# Digital_Port_F_State_LED_Inducator.net
KiCad netlist of a schematic drawn in Altium Designer
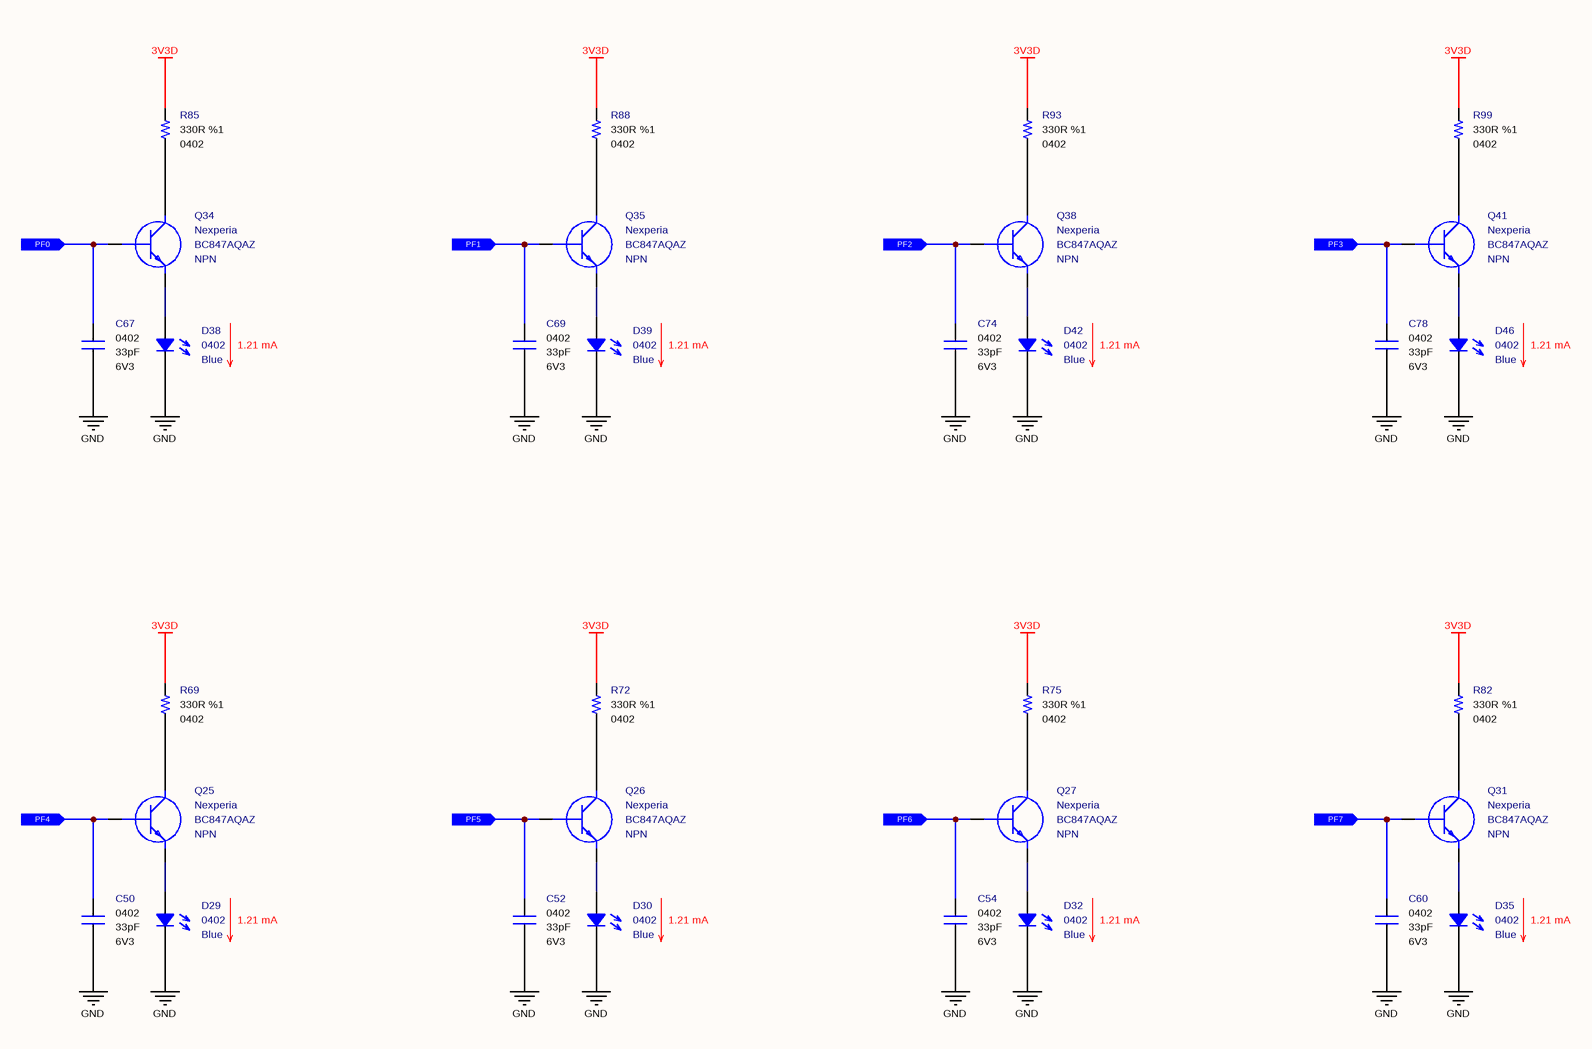
[diagram p0: Digital Port F State LED Inducator.SchDoc]

(export (version "E")
  (design (tool "Eeschema 10.0.6"))
  (components
    (comp (ref "C50")
      (value "33pF")
      (footprint "CAPACITOR_0402")
      (description "Capacitor - 33pF [0402] (Ceramic)")
      (fields
        (field (name "CASE") "0402")
        (field (name "TOLERANCE") "10%")
        (field (name "VOLTAGE") "6V3")
        (field (name "MANUFACTURER PART NUMBER") "C0402C330J9RACAUTO")
      )
      (libsource (lib "Ovoo_Library") (part "Capacitor - 33pF [0402-6V3]"))
    )
    (comp (ref "C52")
      (value "33pF")
      (footprint "CAPACITOR_0402")
      (description "Capacitor - 33pF [0402] (Ceramic)")
      (fields
        (field (name "CASE") "0402")
        (field (name "TOLERANCE") "10%")
        (field (name "VOLTAGE") "6V3")
        (field (name "MANUFACTURER PART NUMBER") "C0402C330J9RACAUTO")
      )
      (libsource (lib "Ovoo_Library") (part "Capacitor - 33pF [0402-6V3]"))
    )
    (comp (ref "C54")
      (value "33pF")
      (footprint "CAPACITOR_0402")
      (description "Capacitor - 33pF [0402] (Ceramic)")
      (fields
        (field (name "CASE") "0402")
        (field (name "TOLERANCE") "10%")
        (field (name "VOLTAGE") "6V3")
        (field (name "MANUFACTURER PART NUMBER") "C0402C330J9RACAUTO")
      )
      (libsource (lib "Ovoo_Library") (part "Capacitor - 33pF [0402-6V3]"))
    )
    (comp (ref "C60")
      (value "33pF")
      (footprint "CAPACITOR_0402")
      (description "Capacitor - 33pF [0402] (Ceramic)")
      (fields
        (field (name "CASE") "0402")
        (field (name "TOLERANCE") "10%")
        (field (name "VOLTAGE") "6V3")
        (field (name "MANUFACTURER PART NUMBER") "C0402C330J9RACAUTO")
      )
      (libsource (lib "Ovoo_Library") (part "Capacitor - 33pF [0402-6V3]"))
    )
    (comp (ref "C67")
      (value "33pF")
      (footprint "CAPACITOR_0402")
      (description "Capacitor - 33pF [0402] (Ceramic)")
      (fields
        (field (name "CASE") "0402")
        (field (name "TOLERANCE") "10%")
        (field (name "VOLTAGE") "6V3")
        (field (name "MANUFACTURER PART NUMBER") "C0402C330J9RACAUTO")
      )
      (libsource (lib "Ovoo_Library") (part "Capacitor - 33pF [0402-6V3]"))
    )
    (comp (ref "C69")
      (value "33pF")
      (footprint "CAPACITOR_0402")
      (description "Capacitor - 33pF [0402] (Ceramic)")
      (fields
        (field (name "CASE") "0402")
        (field (name "TOLERANCE") "10%")
        (field (name "VOLTAGE") "6V3")
        (field (name "MANUFACTURER PART NUMBER") "C0402C330J9RACAUTO")
      )
      (libsource (lib "Ovoo_Library") (part "Capacitor - 33pF [0402-6V3]"))
    )
    (comp (ref "C74")
      (value "33pF")
      (footprint "CAPACITOR_0402")
      (description "Capacitor - 33pF [0402] (Ceramic)")
      (fields
        (field (name "CASE") "0402")
        (field (name "TOLERANCE") "10%")
        (field (name "VOLTAGE") "6V3")
        (field (name "MANUFACTURER PART NUMBER") "C0402C330J9RACAUTO")
      )
      (libsource (lib "Ovoo_Library") (part "Capacitor - 33pF [0402-6V3]"))
    )
    (comp (ref "C78")
      (value "33pF")
      (footprint "CAPACITOR_0402")
      (description "Capacitor - 33pF [0402] (Ceramic)")
      (fields
        (field (name "CASE") "0402")
        (field (name "TOLERANCE") "10%")
        (field (name "VOLTAGE") "6V3")
        (field (name "MANUFACTURER PART NUMBER") "C0402C330J9RACAUTO")
      )
      (libsource (lib "Ovoo_Library") (part "Capacitor - 33pF [0402-6V3]"))
    )
    (comp (ref "D29")
      (value "SMD LED (Blue)")
      (footprint "LED_0402")
      (description "Standard LEDs - SMD PICOLEDTM;BLUE LED; 25M @ 5MA")
      (fields
        (field (name "MANUFACTURER_PART_NUMBER") "SMLP13BC8TT86")
        (field (name "MOUSER_PART_NUMBER") "755-SMLP13BC8TT86")
        (field (name "CASE") "0402")
        (field (name "COLOR") "Blue")
      )
      (libsource (lib "Ovoo_Library") (part "Diode - LED (0402-Blue)"))
    )
    (comp (ref "D30")
      (value "SMD LED (Blue)")
      (footprint "LED_0402")
      (description "Standard LEDs - SMD PICOLEDTM;BLUE LED; 25M @ 5MA")
      (fields
        (field (name "MANUFACTURER_PART_NUMBER") "SMLP13BC8TT86")
        (field (name "MOUSER_PART_NUMBER") "755-SMLP13BC8TT86")
        (field (name "CASE") "0402")
        (field (name "COLOR") "Blue")
      )
      (libsource (lib "Ovoo_Library") (part "Diode - LED (0402-Blue)"))
    )
    (comp (ref "D32")
      (value "SMD LED (Blue)")
      (footprint "LED_0402")
      (description "Standard LEDs - SMD PICOLEDTM;BLUE LED; 25M @ 5MA")
      (fields
        (field (name "MANUFACTURER_PART_NUMBER") "SMLP13BC8TT86")
        (field (name "MOUSER_PART_NUMBER") "755-SMLP13BC8TT86")
        (field (name "CASE") "0402")
        (field (name "COLOR") "Blue")
      )
      (libsource (lib "Ovoo_Library") (part "Diode - LED (0402-Blue)"))
    )
    (comp (ref "D35")
      (value "SMD LED (Blue)")
      (footprint "LED_0402")
      (description "Standard LEDs - SMD PICOLEDTM;BLUE LED; 25M @ 5MA")
      (fields
        (field (name "MANUFACTURER_PART_NUMBER") "SMLP13BC8TT86")
        (field (name "MOUSER_PART_NUMBER") "755-SMLP13BC8TT86")
        (field (name "CASE") "0402")
        (field (name "COLOR") "Blue")
      )
      (libsource (lib "Ovoo_Library") (part "Diode - LED (0402-Blue)"))
    )
    (comp (ref "D38")
      (value "SMD LED (Blue)")
      (footprint "LED_0402")
      (description "Standard LEDs - SMD PICOLEDTM;BLUE LED; 25M @ 5MA")
      (fields
        (field (name "MANUFACTURER_PART_NUMBER") "SMLP13BC8TT86")
        (field (name "MOUSER_PART_NUMBER") "755-SMLP13BC8TT86")
        (field (name "CASE") "0402")
        (field (name "COLOR") "Blue")
      )
      (libsource (lib "Ovoo_Library") (part "Diode - LED (0402-Blue)"))
    )
    (comp (ref "D39")
      (value "SMD LED (Blue)")
      (footprint "LED_0402")
      (description "Standard LEDs - SMD PICOLEDTM;BLUE LED; 25M @ 5MA")
      (fields
        (field (name "MANUFACTURER_PART_NUMBER") "SMLP13BC8TT86")
        (field (name "MOUSER_PART_NUMBER") "755-SMLP13BC8TT86")
        (field (name "CASE") "0402")
        (field (name "COLOR") "Blue")
      )
      (libsource (lib "Ovoo_Library") (part "Diode - LED (0402-Blue)"))
    )
    (comp (ref "D42")
      (value "SMD LED (Blue)")
      (footprint "LED_0402")
      (description "Standard LEDs - SMD PICOLEDTM;BLUE LED; 25M @ 5MA")
      (fields
        (field (name "MANUFACTURER_PART_NUMBER") "SMLP13BC8TT86")
        (field (name "MOUSER_PART_NUMBER") "755-SMLP13BC8TT86")
        (field (name "CASE") "0402")
        (field (name "COLOR") "Blue")
      )
      (libsource (lib "Ovoo_Library") (part "Diode - LED (0402-Blue)"))
    )
    (comp (ref "D46")
      (value "SMD LED (Blue)")
      (footprint "LED_0402")
      (description "Standard LEDs - SMD PICOLEDTM;BLUE LED; 25M @ 5MA")
      (fields
        (field (name "MANUFACTURER_PART_NUMBER") "SMLP13BC8TT86")
        (field (name "MOUSER_PART_NUMBER") "755-SMLP13BC8TT86")
        (field (name "CASE") "0402")
        (field (name "COLOR") "Blue")
      )
      (libsource (lib "Ovoo_Library") (part "Diode - LED (0402-Blue)"))
    )
    (comp (ref "Q25")
      (value "Bipolar NPN Transistors")
      (footprint "SOT1215")
      (description "Bipolar Transistors - BJT BC847AQA/DFN1010D-3/REEL 7\" Q2")
      (fields
        (field (name "MOUSER_PART_NUMBER") "771-BC847AQAZ")
        (field (name "MANUFACTURER_NAME") "Nexperia")
        (field (name "MANUFACTURER_PART_NUMBER") "BC847AQAZ")
        (field (name "POLARITY") "NPN")
      )
      (libsource (lib "Ovoo_Library") (part "Transistor - BC847"))
    )
    (comp (ref "Q26")
      (value "Bipolar NPN Transistors")
      (footprint "SOT1215")
      (description "Bipolar Transistors - BJT BC847AQA/DFN1010D-3/REEL 7\" Q2")
      (fields
        (field (name "MOUSER_PART_NUMBER") "771-BC847AQAZ")
        (field (name "MANUFACTURER_NAME") "Nexperia")
        (field (name "MANUFACTURER_PART_NUMBER") "BC847AQAZ")
        (field (name "POLARITY") "NPN")
      )
      (libsource (lib "Ovoo_Library") (part "Transistor - BC847"))
    )
    (comp (ref "Q27")
      (value "Bipolar NPN Transistors")
      (footprint "SOT1215")
      (description "Bipolar Transistors - BJT BC847AQA/DFN1010D-3/REEL 7\" Q2")
      (fields
        (field (name "MOUSER_PART_NUMBER") "771-BC847AQAZ")
        (field (name "MANUFACTURER_NAME") "Nexperia")
        (field (name "MANUFACTURER_PART_NUMBER") "BC847AQAZ")
        (field (name "POLARITY") "NPN")
      )
      (libsource (lib "Ovoo_Library") (part "Transistor - BC847"))
    )
    (comp (ref "Q31")
      (value "Bipolar NPN Transistors")
      (footprint "SOT1215")
      (description "Bipolar Transistors - BJT BC847AQA/DFN1010D-3/REEL 7\" Q2")
      (fields
        (field (name "MOUSER_PART_NUMBER") "771-BC847AQAZ")
        (field (name "MANUFACTURER_NAME") "Nexperia")
        (field (name "MANUFACTURER_PART_NUMBER") "BC847AQAZ")
        (field (name "POLARITY") "NPN")
      )
      (libsource (lib "Ovoo_Library") (part "Transistor - BC847"))
    )
    (comp (ref "Q34")
      (value "Bipolar NPN Transistors")
      (footprint "SOT1215")
      (description "Bipolar Transistors - BJT BC847AQA/DFN1010D-3/REEL 7\" Q2")
      (fields
        (field (name "MOUSER_PART_NUMBER") "771-BC847AQAZ")
        (field (name "MANUFACTURER_NAME") "Nexperia")
        (field (name "MANUFACTURER_PART_NUMBER") "BC847AQAZ")
        (field (name "POLARITY") "NPN")
      )
      (libsource (lib "Ovoo_Library") (part "Transistor - BC847"))
    )
    (comp (ref "Q35")
      (value "Bipolar NPN Transistors")
      (footprint "SOT1215")
      (description "Bipolar Transistors - BJT BC847AQA/DFN1010D-3/REEL 7\" Q2")
      (fields
        (field (name "MOUSER_PART_NUMBER") "771-BC847AQAZ")
        (field (name "MANUFACTURER_NAME") "Nexperia")
        (field (name "MANUFACTURER_PART_NUMBER") "BC847AQAZ")
        (field (name "POLARITY") "NPN")
      )
      (libsource (lib "Ovoo_Library") (part "Transistor - BC847"))
    )
    (comp (ref "Q38")
      (value "Bipolar NPN Transistors")
      (footprint "SOT1215")
      (description "Bipolar Transistors - BJT BC847AQA/DFN1010D-3/REEL 7\" Q2")
      (fields
        (field (name "MOUSER_PART_NUMBER") "771-BC847AQAZ")
        (field (name "MANUFACTURER_NAME") "Nexperia")
        (field (name "MANUFACTURER_PART_NUMBER") "BC847AQAZ")
        (field (name "POLARITY") "NPN")
      )
      (libsource (lib "Ovoo_Library") (part "Transistor - BC847"))
    )
    (comp (ref "Q41")
      (value "Bipolar NPN Transistors")
      (footprint "SOT1215")
      (description "Bipolar Transistors - BJT BC847AQA/DFN1010D-3/REEL 7\" Q2")
      (fields
        (field (name "MOUSER_PART_NUMBER") "771-BC847AQAZ")
        (field (name "MANUFACTURER_NAME") "Nexperia")
        (field (name "MANUFACTURER_PART_NUMBER") "BC847AQAZ")
        (field (name "POLARITY") "NPN")
      )
      (libsource (lib "Ovoo_Library") (part "Transistor - BC847"))
    )
    (comp (ref "R69")
      (value "330R")
      (footprint "RESISTOR_0402")
      (description "Thick Film Resistors - SMD 1/16 W 330 Ohm 1%")
      (fields
        (field (name "TOLERANCE") "%1")
        (field (name "CASE") "0402")
        (field (name "MANUFACTURER PART NUMBER") "CRCW0402330RFKED")
        (field (name "MOUSER PART NUMBER") "71-CRCW0402-330-E3")
      )
      (libsource (lib "Ovoo_Library") (part "Resistor - 330R"))
    )
    (comp (ref "R72")
      (value "330R")
      (footprint "RESISTOR_0402")
      (description "Thick Film Resistors - SMD 1/16 W 330 Ohm 1%")
      (fields
        (field (name "TOLERANCE") "%1")
        (field (name "CASE") "0402")
        (field (name "MANUFACTURER PART NUMBER") "CRCW0402330RFKED")
        (field (name "MOUSER PART NUMBER") "71-CRCW0402-330-E3")
      )
      (libsource (lib "Ovoo_Library") (part "Resistor - 330R"))
    )
    (comp (ref "R75")
      (value "330R")
      (footprint "RESISTOR_0402")
      (description "Thick Film Resistors - SMD 1/16 W 330 Ohm 1%")
      (fields
        (field (name "TOLERANCE") "%1")
        (field (name "CASE") "0402")
        (field (name "MANUFACTURER PART NUMBER") "CRCW0402330RFKED")
        (field (name "MOUSER PART NUMBER") "71-CRCW0402-330-E3")
      )
      (libsource (lib "Ovoo_Library") (part "Resistor - 330R"))
    )
    (comp (ref "R82")
      (value "330R")
      (footprint "RESISTOR_0402")
      (description "Thick Film Resistors - SMD 1/16 W 330 Ohm 1%")
      (fields
        (field (name "TOLERANCE") "%1")
        (field (name "CASE") "0402")
        (field (name "MANUFACTURER PART NUMBER") "CRCW0402330RFKED")
        (field (name "MOUSER PART NUMBER") "71-CRCW0402-330-E3")
      )
      (libsource (lib "Ovoo_Library") (part "Resistor - 330R"))
    )
    (comp (ref "R85")
      (value "330R")
      (footprint "RESISTOR_0402")
      (description "Thick Film Resistors - SMD 1/16 W 330 Ohm 1%")
      (fields
        (field (name "TOLERANCE") "%1")
        (field (name "CASE") "0402")
        (field (name "MANUFACTURER PART NUMBER") "CRCW0402330RFKED")
        (field (name "MOUSER PART NUMBER") "71-CRCW0402-330-E3")
      )
      (libsource (lib "Ovoo_Library") (part "Resistor - 330R"))
    )
    (comp (ref "R88")
      (value "330R")
      (footprint "RESISTOR_0402")
      (description "Thick Film Resistors - SMD 1/16 W 330 Ohm 1%")
      (fields
        (field (name "TOLERANCE") "%1")
        (field (name "CASE") "0402")
        (field (name "MANUFACTURER PART NUMBER") "CRCW0402330RFKED")
        (field (name "MOUSER PART NUMBER") "71-CRCW0402-330-E3")
      )
      (libsource (lib "Ovoo_Library") (part "Resistor - 330R"))
    )
    (comp (ref "R93")
      (value "330R")
      (footprint "RESISTOR_0402")
      (description "Thick Film Resistors - SMD 1/16 W 330 Ohm 1%")
      (fields
        (field (name "TOLERANCE") "%1")
        (field (name "CASE") "0402")
        (field (name "MANUFACTURER PART NUMBER") "CRCW0402330RFKED")
        (field (name "MOUSER PART NUMBER") "71-CRCW0402-330-E3")
      )
      (libsource (lib "Ovoo_Library") (part "Resistor - 330R"))
    )
    (comp (ref "R99")
      (value "330R")
      (footprint "RESISTOR_0402")
      (description "Thick Film Resistors - SMD 1/16 W 330 Ohm 1%")
      (fields
        (field (name "TOLERANCE") "%1")
        (field (name "CASE") "0402")
        (field (name "MANUFACTURER PART NUMBER") "CRCW0402330RFKED")
        (field (name "MOUSER PART NUMBER") "71-CRCW0402-330-E3")
      )
      (libsource (lib "Ovoo_Library") (part "Resistor - 330R"))
    )
  )
  (nets
    (net (code "1") (name "/PF0") (class "Default")
      (node (ref "C67") (pin "1") (pinfunction "1_1") (pintype "passive"))
      (node (ref "Q34") (pin "1") (pinfunction "B_1") (pintype "passive"))
    )
    (net (code "2") (name "/PF1") (class "Default")
      (node (ref "C69") (pin "1") (pinfunction "1_1") (pintype "passive"))
      (node (ref "Q35") (pin "1") (pinfunction "B_1") (pintype "passive"))
    )
    (net (code "3") (name "/PF2") (class "Default")
      (node (ref "C74") (pin "1") (pinfunction "1_1") (pintype "passive"))
      (node (ref "Q38") (pin "1") (pinfunction "B_1") (pintype "passive"))
    )
    (net (code "4") (name "/PF3") (class "Default")
      (node (ref "C78") (pin "1") (pinfunction "1_1") (pintype "passive"))
      (node (ref "Q41") (pin "1") (pinfunction "B_1") (pintype "passive"))
    )
    (net (code "5") (name "/PF4") (class "Default")
      (node (ref "C50") (pin "1") (pinfunction "1_1") (pintype "passive"))
      (node (ref "Q25") (pin "1") (pinfunction "B_1") (pintype "passive"))
    )
    (net (code "6") (name "/PF5") (class "Default")
      (node (ref "C52") (pin "1") (pinfunction "1_1") (pintype "passive"))
      (node (ref "Q26") (pin "1") (pinfunction "B_1") (pintype "passive"))
    )
    (net (code "7") (name "/PF6") (class "Default")
      (node (ref "C54") (pin "1") (pinfunction "1_1") (pintype "passive"))
      (node (ref "Q27") (pin "1") (pinfunction "B_1") (pintype "passive"))
    )
    (net (code "8") (name "/PF7") (class "Default")
      (node (ref "C60") (pin "1") (pinfunction "1_1") (pintype "passive"))
      (node (ref "Q31") (pin "1") (pinfunction "B_1") (pintype "passive"))
    )
    (net (code "9") (name "3V3D") (class "Default")
      (node (ref "R69") (pin "2") (pinfunction "2_2") (pintype "passive"))
      (node (ref "R72") (pin "2") (pinfunction "2_2") (pintype "passive"))
      (node (ref "R75") (pin "2") (pinfunction "2_2") (pintype "passive"))
      (node (ref "R82") (pin "2") (pinfunction "2_2") (pintype "passive"))
      (node (ref "R85") (pin "2") (pinfunction "2_2") (pintype "passive"))
      (node (ref "R88") (pin "2") (pinfunction "2_2") (pintype "passive"))
      (node (ref "R93") (pin "2") (pinfunction "2_2") (pintype "passive"))
      (node (ref "R99") (pin "2") (pinfunction "2_2") (pintype "passive"))
    )
    (net (code "10") (name "GND") (class "Default")
      (node (ref "C50") (pin "2") (pinfunction "2_2") (pintype "passive"))
      (node (ref "C52") (pin "2") (pinfunction "2_2") (pintype "passive"))
      (node (ref "C54") (pin "2") (pinfunction "2_2") (pintype "passive"))
      (node (ref "C60") (pin "2") (pinfunction "2_2") (pintype "passive"))
      (node (ref "C67") (pin "2") (pinfunction "2_2") (pintype "passive"))
      (node (ref "C69") (pin "2") (pinfunction "2_2") (pintype "passive"))
      (node (ref "C74") (pin "2") (pinfunction "2_2") (pintype "passive"))
      (node (ref "C78") (pin "2") (pinfunction "2_2") (pintype "passive"))
      (node (ref "D29") (pin "1") (pinfunction "1_1") (pintype "passive"))
      (node (ref "D30") (pin "1") (pinfunction "1_1") (pintype "passive"))
      (node (ref "D32") (pin "1") (pinfunction "1_1") (pintype "passive"))
      (node (ref "D35") (pin "1") (pinfunction "1_1") (pintype "passive"))
      (node (ref "D38") (pin "1") (pinfunction "1_1") (pintype "passive"))
      (node (ref "D39") (pin "1") (pinfunction "1_1") (pintype "passive"))
      (node (ref "D42") (pin "1") (pinfunction "1_1") (pintype "passive"))
      (node (ref "D46") (pin "1") (pinfunction "1_1") (pintype "passive"))
    )
    (net (code "11") (name "Net-(Q25-C)") (class "Default")
      (node (ref "Q25") (pin "3") (pinfunction "C_3") (pintype "passive"))
      (node (ref "R69") (pin "1") (pinfunction "1_1") (pintype "passive"))
    )
    (net (code "12") (name "Net-(Q25-E)") (class "Default")
      (node (ref "D29") (pin "2") (pinfunction "2_2") (pintype "passive"))
      (node (ref "Q25") (pin "2") (pinfunction "E_2") (pintype "passive"))
    )
    (net (code "13") (name "Net-(Q26-C)") (class "Default")
      (node (ref "Q26") (pin "3") (pinfunction "C_3") (pintype "passive"))
      (node (ref "R72") (pin "1") (pinfunction "1_1") (pintype "passive"))
    )
    (net (code "14") (name "Net-(Q26-E)") (class "Default")
      (node (ref "D30") (pin "2") (pinfunction "2_2") (pintype "passive"))
      (node (ref "Q26") (pin "2") (pinfunction "E_2") (pintype "passive"))
    )
    (net (code "15") (name "Net-(Q27-C)") (class "Default")
      (node (ref "Q27") (pin "3") (pinfunction "C_3") (pintype "passive"))
      (node (ref "R75") (pin "1") (pinfunction "1_1") (pintype "passive"))
    )
    (net (code "16") (name "Net-(Q27-E)") (class "Default")
      (node (ref "D32") (pin "2") (pinfunction "2_2") (pintype "passive"))
      (node (ref "Q27") (pin "2") (pinfunction "E_2") (pintype "passive"))
    )
    (net (code "17") (name "Net-(Q31-C)") (class "Default")
      (node (ref "Q31") (pin "3") (pinfunction "C_3") (pintype "passive"))
      (node (ref "R82") (pin "1") (pinfunction "1_1") (pintype "passive"))
    )
    (net (code "18") (name "Net-(Q31-E)") (class "Default")
      (node (ref "D35") (pin "2") (pinfunction "2_2") (pintype "passive"))
      (node (ref "Q31") (pin "2") (pinfunction "E_2") (pintype "passive"))
    )
    (net (code "19") (name "Net-(Q34-C)") (class "Default")
      (node (ref "Q34") (pin "3") (pinfunction "C_3") (pintype "passive"))
      (node (ref "R85") (pin "1") (pinfunction "1_1") (pintype "passive"))
    )
    (net (code "20") (name "Net-(Q34-E)") (class "Default")
      (node (ref "D38") (pin "2") (pinfunction "2_2") (pintype "passive"))
      (node (ref "Q34") (pin "2") (pinfunction "E_2") (pintype "passive"))
    )
    (net (code "21") (name "Net-(Q35-C)") (class "Default")
      (node (ref "Q35") (pin "3") (pinfunction "C_3") (pintype "passive"))
      (node (ref "R88") (pin "1") (pinfunction "1_1") (pintype "passive"))
    )
    (net (code "22") (name "Net-(Q35-E)") (class "Default")
      (node (ref "D39") (pin "2") (pinfunction "2_2") (pintype "passive"))
      (node (ref "Q35") (pin "2") (pinfunction "E_2") (pintype "passive"))
    )
    (net (code "23") (name "Net-(Q38-C)") (class "Default")
      (node (ref "Q38") (pin "3") (pinfunction "C_3") (pintype "passive"))
      (node (ref "R93") (pin "1") (pinfunction "1_1") (pintype "passive"))
    )
    (net (code "24") (name "Net-(Q38-E)") (class "Default")
      (node (ref "D42") (pin "2") (pinfunction "2_2") (pintype "passive"))
      (node (ref "Q38") (pin "2") (pinfunction "E_2") (pintype "passive"))
    )
    (net (code "25") (name "Net-(Q41-C)") (class "Default")
      (node (ref "Q41") (pin "3") (pinfunction "C_3") (pintype "passive"))
      (node (ref "R99") (pin "1") (pinfunction "1_1") (pintype "passive"))
    )
    (net (code "26") (name "Net-(Q41-E)") (class "Default")
      (node (ref "D46") (pin "2") (pinfunction "2_2") (pintype "passive"))
      (node (ref "Q41") (pin "2") (pinfunction "E_2") (pintype "passive"))
    )
  )
)
